# TS_Measurement_Circuit.net
KiCad netlist of a schematic drawn in Altium Designer
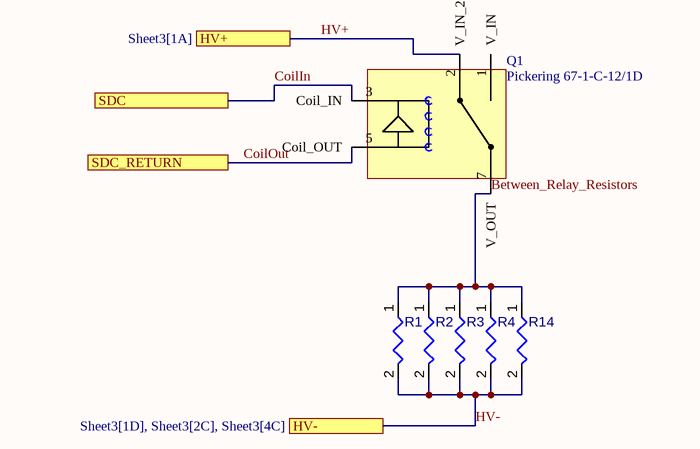
[diagram p0: TS_Measurement_Circuit.SchDoc]

(export (version "E")
  (design (tool "Eeschema 10.0.6"))
  (components
    (comp (ref "Q1")
      (value "Pickering 67-1-C-12/1D")
      (description "https://www.pickeringrelay.com/pdfs/67-68-high-voltage-reed-relays.pdf")
      (libsource (lib "Alt_ium Course") (part "Pickering 67-1-A-12_1D-Symbol-1"))
    )
    (comp (ref "R1")
      (value "RH02530K00FC02")
      (description "30 kΩ, 25 W, 800 V")
      (libsource (lib "Alt_ium Course") (part "RES-2"))
    )
    (comp (ref "R2")
      (value "RH02530K00FC02")
      (description "30 kΩ, 25 W, 800 V")
      (libsource (lib "Alt_ium Course") (part "RES-2"))
    )
    (comp (ref "R3")
      (value "RH02530K00FC02")
      (description "30 kΩ, 25 W, 800 V")
      (libsource (lib "Alt_ium Course") (part "RES-2"))
    )
    (comp (ref "R4")
      (value "RH02530K00FC02")
      (description "30 kΩ, 25 W, 800 V")
      (libsource (lib "Alt_ium Course") (part "RES-2"))
    )
    (comp (ref "R14")
      (value "RH02530K00FC02")
      (description "30 kΩ, 25 W, 800 V")
      (libsource (lib "Alt_ium Course") (part "RES-2"))
    )
  )
  (nets
    (net (code "1") (name "/Between_Relay_Resistors") (class "Default")
      (node (ref "R1") (pin "1") (pinfunction "1_1") (pintype "passive"))
      (node (ref "R14") (pin "1") (pinfunction "1_1") (pintype "passive"))
      (node (ref "R2") (pin "1") (pinfunction "1_1") (pintype "passive"))
      (node (ref "R3") (pin "1") (pinfunction "1_1") (pintype "passive"))
      (node (ref "R4") (pin "1") (pinfunction "1_1") (pintype "passive"))
    )
    (net (code "5") (name "/HV-") (class "Default")
      (node (ref "R1") (pin "2") (pinfunction "2_2") (pintype "passive"))
      (node (ref "R14") (pin "2") (pinfunction "2_2") (pintype "passive"))
      (node (ref "R2") (pin "2") (pinfunction "2_2") (pintype "passive"))
      (node (ref "R3") (pin "2") (pinfunction "2_2") (pintype "passive"))
      (node (ref "R4") (pin "2") (pinfunction "2_2") (pintype "passive"))
    )
    (net (code "6") (name "unconnected-(Q1-Coil_IN-Pad3)") (class "Default")
      (node (ref "Q1") (pin "3") (pinfunction "Coil_IN_3") (pintype "passive"))
    )
    (net (code "7") (name "unconnected-(Q1-Coil_OUT-Pad5)") (class "Default")
      (node (ref "Q1") (pin "5") (pinfunction "Coil_OUT_5") (pintype "passive"))
    )
    (net (code "8") (name "unconnected-(Q1-V_IN-Pad1)") (class "Default")
      (node (ref "Q1") (pin "1") (pinfunction "V_IN_1") (pintype "passive"))
    )
    (net (code "9") (name "unconnected-(Q1-V_IN_2-Pad2)") (class "Default")
      (node (ref "Q1") (pin "2") (pinfunction "V_IN_2_2") (pintype "passive"))
    )
    (net (code "10") (name "unconnected-(Q1-V_OUT-Pad7)") (class "Default")
      (node (ref "Q1") (pin "7") (pinfunction "V_OUT_7") (pintype "passive"))
    )
  )
)
